# Featured_Tag_RBS020902T.net
KiCad netlist of a schematic drawn in Altium Designer
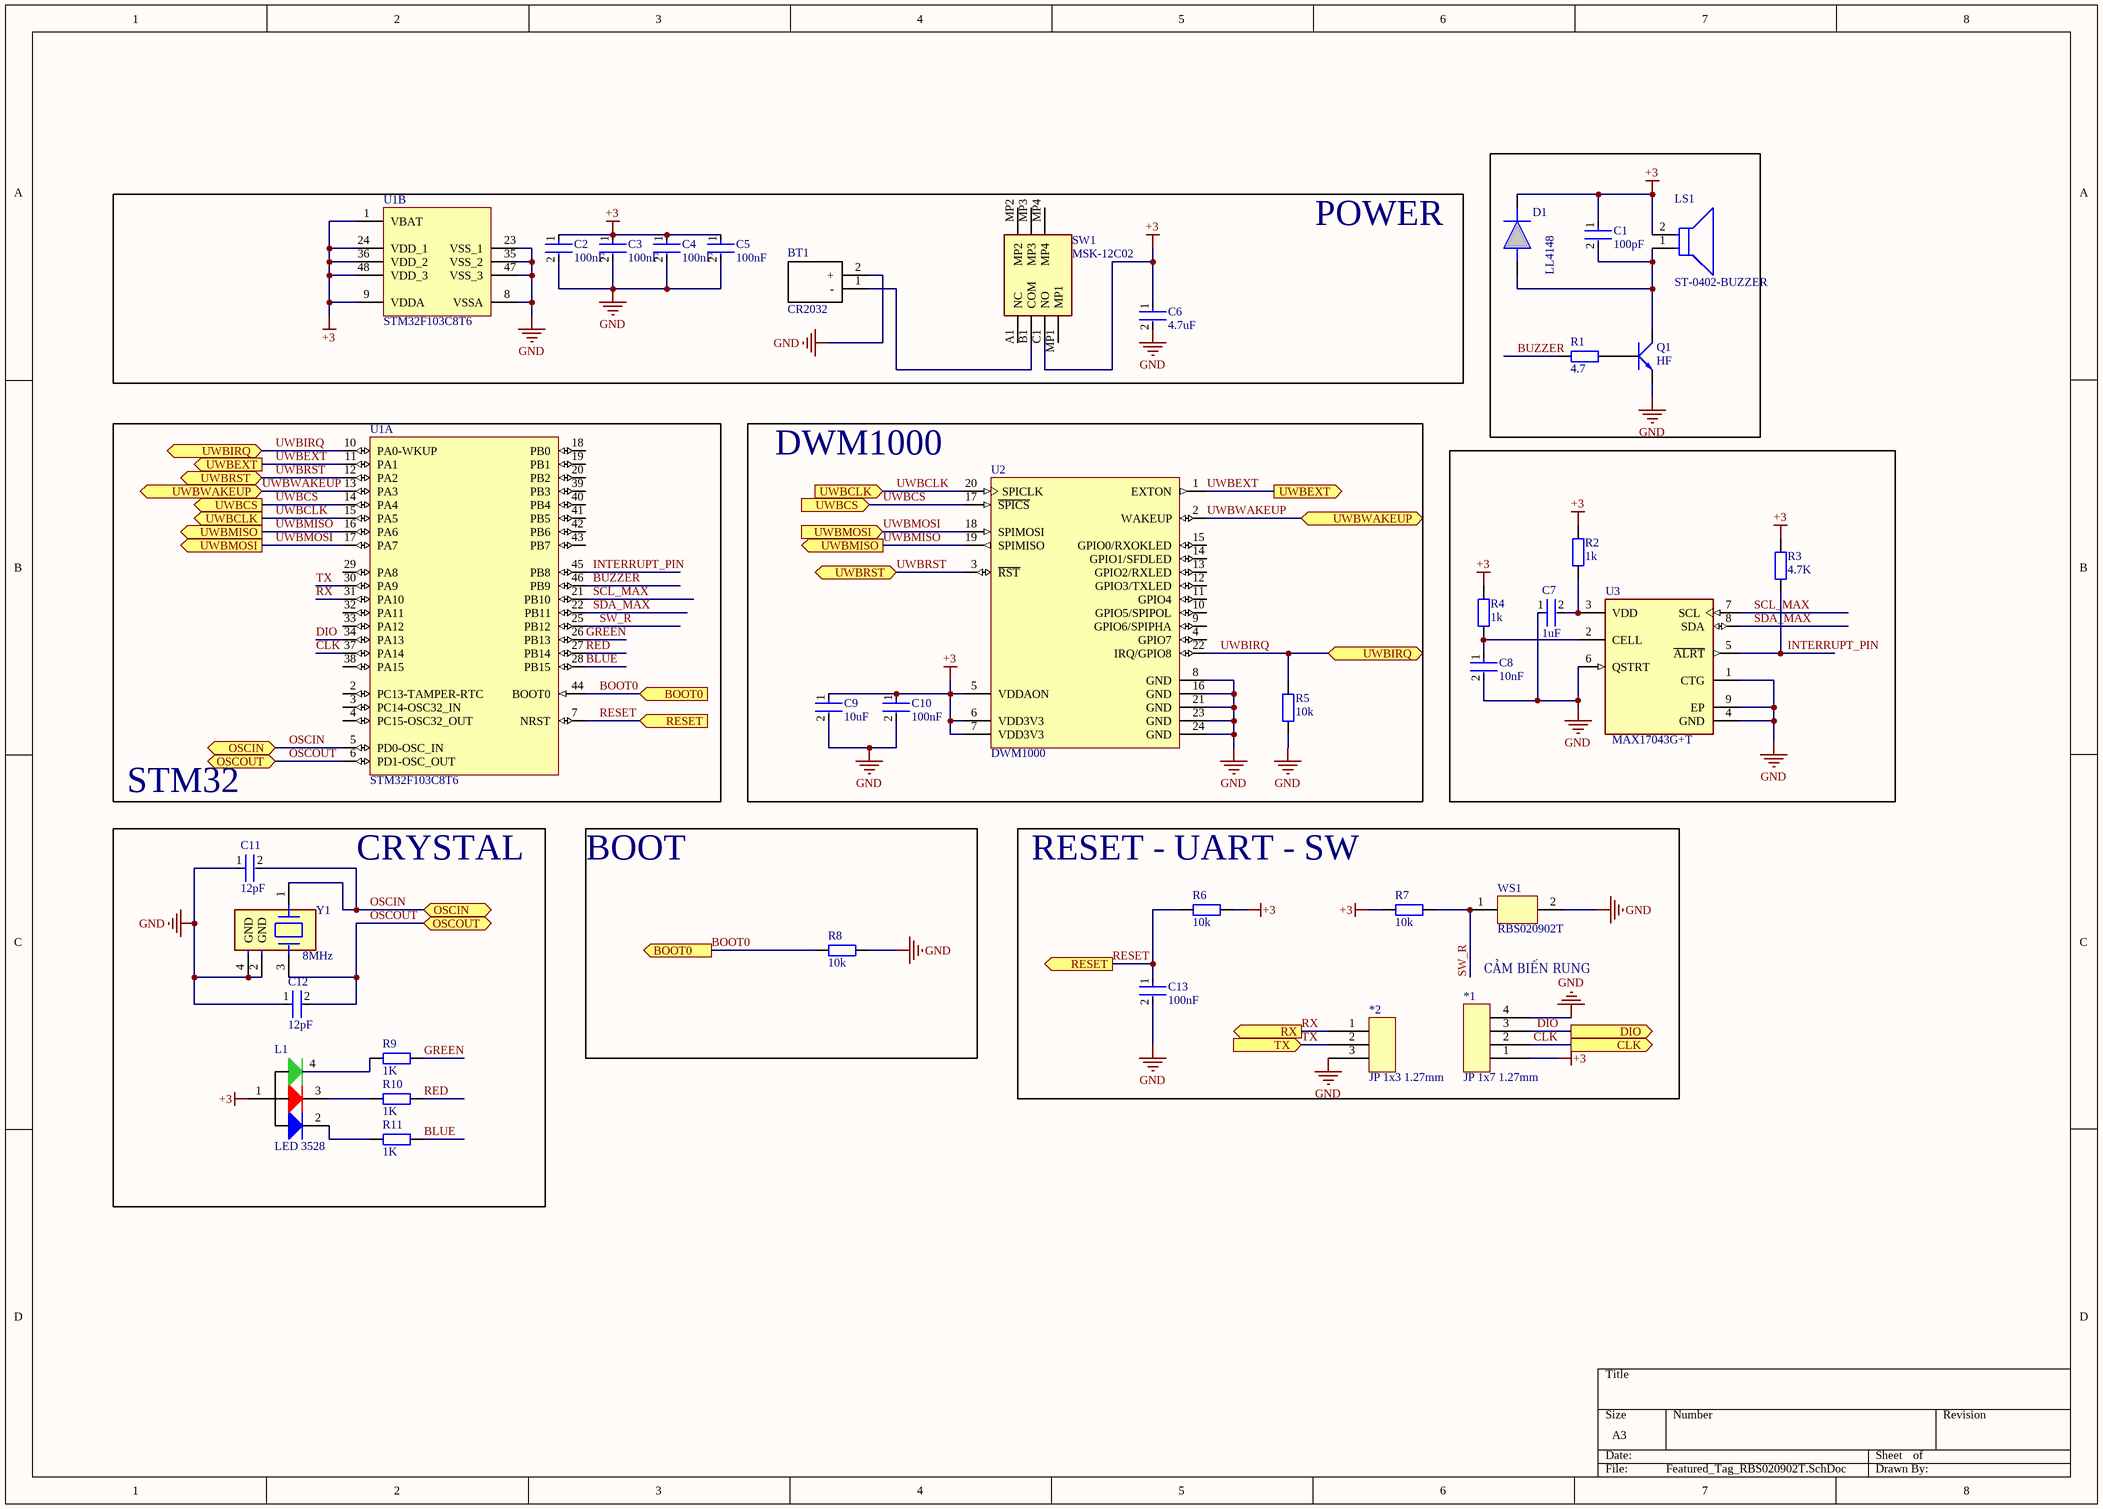
[diagram p0: Featured_Tag_RBS020902T.SchDoc]

(export (version "E")
  (design (tool "Eeschema 10.0.6"))
  (components
    (comp (ref "*1")
      (value "JP 1x7 1.27mm")
      (footprint "JP 1x4 1.27mm")
      (libsource (lib "Schlib1") (part "JP 1x7 1.27mm"))
    )
    (comp (ref "*2")
      (value "JP 1x3 1.27mm")
      (footprint "JP 1x3 1.27mm")
      (libsource (lib "Schlib1") (part "JP 1x3 1.27mm"))
    )
    (comp (ref "BT1")
      (value "CR2032")
      (footprint "SamacSys:CR2450NFHLF")
      (description "Battery")
      (fields
        (field (name "MANUFACTURER_PART_NUMBER") "CR2450NFH-LF")
        (field (name "MOUSER PART NUMBER") "614-CR2450NFH-LF")
      )
      (libsource (lib "*") (part "CR2450NFH-LF"))
    )
    (comp (ref "C1")
      (value "100pF")
      (footprint "FP-0603-L_1_6_0_15-W_0_81-MFG")
      (description "General Purpose Ceramic Capacitor, 0603, 33nF, 5%, X7R, 15%, 16V")
      (fields (field (name "TOLERANCE") "5%"))
      (libsource (lib "Altium Content Vault") (part "02cd4be3c70576c341d710602a673aa"))
    )
    (comp (ref "C2")
      (value "100nF")
      (footprint "FP-0603-L_1_6_0_15-W_0_81-MFG")
      (description "General Purpose Ceramic Capacitor, 0603, 33nF, 5%, X7R, 15%, 16V")
      (fields (field (name "TOLERANCE") "5%"))
      (libsource (lib "Altium Content Vault") (part "02cd4be3c70576c341d710602a673aa"))
    )
    (comp (ref "C3")
      (value "100nF")
      (footprint "FP-0603-L_1_6_0_15-W_0_81-MFG")
      (description "General Purpose Ceramic Capacitor, 0603, 33nF, 5%, X7R, 15%, 16V")
      (fields (field (name "TOLERANCE") "5%"))
      (libsource (lib "Altium Content Vault") (part "02cd4be3c70576c341d710602a673aa"))
    )
    (comp (ref "C4")
      (value "100nF")
      (footprint "FP-0603-L_1_6_0_15-W_0_81-MFG")
      (description "General Purpose Ceramic Capacitor, 0603, 33nF, 5%, X7R, 15%, 16V")
      (fields (field (name "TOLERANCE") "5%"))
      (libsource (lib "Altium Content Vault") (part "02cd4be3c70576c341d710602a673aa"))
    )
    (comp (ref "C5")
      (value "100nF")
      (footprint "FP-0603-L_1_6_0_15-W_0_81-MFG")
      (description "General Purpose Ceramic Capacitor, 0603, 33nF, 5%, X7R, 15%, 16V")
      (fields (field (name "TOLERANCE") "5%"))
      (libsource (lib "Altium Content Vault") (part "02cd4be3c70576c341d710602a673aa"))
    )
    (comp (ref "C6")
      (value "4.7uF")
      (footprint "FP-0603-L_1_6_0_15-W_0_81-MFG")
      (description "General Purpose Ceramic Capacitor, 0603, 33nF, 5%, X7R, 15%, 16V")
      (fields (field (name "TOLERANCE") "5%"))
      (libsource (lib "Altium Content Vault") (part "02cd4be3c70576c341d710602a673aa"))
    )
    (comp (ref "C7")
      (value "1uF")
      (footprint "FP-0603-L_1_6_0_15-W_0_81-MFG")
      (description "General Purpose Ceramic Capacitor, 0603, 33nF, 5%, X7R, 15%, 16V")
      (fields (field (name "TOLERANCE") "5%"))
      (libsource (lib "Altium Content Vault") (part "02cd4be3c70576c341d710602a673aa"))
    )
    (comp (ref "C8")
      (value "10nF")
      (footprint "FP-0603-L_1_6_0_15-W_0_81-MFG")
      (description "General Purpose Ceramic Capacitor, 0603, 33nF, 5%, X7R, 15%, 16V")
      (fields (field (name "TOLERANCE") "5%"))
      (libsource (lib "Altium Content Vault") (part "02cd4be3c70576c341d710602a673aa"))
    )
    (comp (ref "C9")
      (value "10uF")
      (footprint "FP-0603-L_1_6_0_15-W_0_81-MFG")
      (description "General Purpose Ceramic Capacitor, 0603, 33nF, 5%, X7R, 15%, 16V")
      (fields (field (name "TOLERANCE") "5%"))
      (libsource (lib "Altium Content Vault") (part "02cd4be3c70576c341d710602a673aa"))
    )
    (comp (ref "C10")
      (value "100nF")
      (footprint "FP-0603-L_1_6_0_15-W_0_81-MFG")
      (description "General Purpose Ceramic Capacitor, 0603, 33nF, 5%, X7R, 15%, 16V")
      (fields (field (name "TOLERANCE") "5%"))
      (libsource (lib "Altium Content Vault") (part "02cd4be3c70576c341d710602a673aa"))
    )
    (comp (ref "C11")
      (value "12pF")
      (footprint "FP-0603-L_1_6_0_15-W_0_81-MFG")
      (description "General Purpose Ceramic Capacitor, 0603, 33nF, 5%, X7R, 15%, 16V")
      (fields (field (name "TOLERANCE") "5%"))
      (libsource (lib "Altium Content Vault") (part "02cd4be3c70576c341d710602a673aa"))
    )
    (comp (ref "C12")
      (value "12pF")
      (footprint "FP-0603-L_1_6_0_15-W_0_81-MFG")
      (description "General Purpose Ceramic Capacitor, 0603, 33nF, 5%, X7R, 15%, 16V")
      (fields (field (name "TOLERANCE") "5%"))
      (libsource (lib "Altium Content Vault") (part "02cd4be3c70576c341d710602a673aa"))
    )
    (comp (ref "C13")
      (value "100nF")
      (footprint "FP-0603-L_1_6_0_15-W_0_81-MFG")
      (description "General Purpose Ceramic Capacitor, 0603, 33nF, 5%, X7R, 15%, 16V")
      (fields (field (name "TOLERANCE") "5%"))
      (libsource (lib "Altium Content Vault") (part "02cd4be3c70576c341d710602a673aa"))
    )
    (comp (ref "D1")
      (value "LL4148")
      (footprint "SOD-80")
      (description "Vishay LL4148-GS18 Switching Diode, 300mA, 2-Pin MiniMELF")
      (fields
        (field (name "MANUFACTURER_PART_NUMBER") "LL4148-GS18")
        (field (name "MOUSER PART NUMBER") "78-LL4148-GS18")
      )
      (libsource (lib "LL4148-GS18") (part "LL4148-GS18"))
    )
    (comp (ref "L1")
      (value "LED 3528")
      (footprint "LED RGB 3528")
      (description "Dán")
      (libsource (lib "Altium_Lib_by_KhueNguyenCreator") (part "LED 3528 RGB"))
    )
    (comp (ref "LS1")
      (value "ST-0402-BUZZER")
      (footprint "FP-ST-0402T-MFG")
      (description "AUDIO MAGNETIC XDCR 2-4V SMD")
      (fields
        (field (name "MANUFACTURER") "Soberton Inc.")
        (field (name "MANUFACTURER PART NUMBER") "ST-0402T")
      )
      (libsource (lib "Altium Content Vault") (part "e749a21513d54f03b70f810f265f423"))
    )
    (comp (ref "Q1")
      (value "HF")
      (footprint "SOT23")
      (description "NPN transistor")
      (libsource (lib "Altium_Lib_by_KhueNguyenCreator") (part "C1815 HF SMD"))
    )
    (comp (ref "R1")
      (value "4.7")
      (footprint "tro smd 0603")
      (description "Dán")
      (libsource (lib "Altium_Lib_by_KhueNguyenCreator") (part "Tro 0603 5% 1k"))
    )
    (comp (ref "R2")
      (value "1k")
      (footprint "tro smd 0603")
      (description "Dán")
      (libsource (lib "Altium_Lib_by_KhueNguyenCreator") (part "Tro 0603 5% 1k"))
    )
    (comp (ref "R3")
      (value "4.7K")
      (footprint "tro smd 0603")
      (description "Dán")
      (libsource (lib "Altium_Lib_by_KhueNguyenCreator") (part "Tro 0603 5% 1k"))
    )
    (comp (ref "R4")
      (value "1k")
      (footprint "tro smd 0603")
      (description "Dán")
      (libsource (lib "Altium_Lib_by_KhueNguyenCreator") (part "Tro 0603 5% 1k"))
    )
    (comp (ref "R5")
      (value "10k")
      (footprint "tro smd 0603")
      (description "Dán")
      (libsource (lib "Altium_Lib_by_KhueNguyenCreator") (part "Tro 0603 5% 10k"))
    )
    (comp (ref "R6")
      (value "10k")
      (footprint "tro smd 0603")
      (description "Dán")
      (libsource (lib "Altium_Lib_by_KhueNguyenCreator") (part "Tro 0603 5% 10k"))
    )
    (comp (ref "R7")
      (value "10k")
      (footprint "tro smd 0603")
      (description "Dán")
      (libsource (lib "Altium_Lib_by_KhueNguyenCreator") (part "Tro 0603 5% 10k"))
    )
    (comp (ref "R8")
      (value "10k")
      (footprint "tro smd 0603")
      (description "Dán")
      (libsource (lib "Altium_Lib_by_KhueNguyenCreator") (part "Tro 0603 5% 10k"))
    )
    (comp (ref "R9")
      (value "1K")
      (footprint "tro smd 0603")
      (description "Dán")
      (libsource (lib "Altium_Lib_by_KhueNguyenCreator") (part "Tro 0603 5% 100R"))
    )
    (comp (ref "R10")
      (value "1K")
      (footprint "tro smd 0603")
      (description "Dán")
      (libsource (lib "Altium_Lib_by_KhueNguyenCreator") (part "Tro 0603 5% 150R"))
    )
    (comp (ref "R11")
      (value "1K")
      (footprint "tro smd 0603")
      (description "Dán")
      (libsource (lib "Altium_Lib_by_KhueNguyenCreator") (part "Tro 0603 5% 100R"))
    )
    (comp (ref "SW1")
      (value "MSK-12C02")
      (footprint "sw_msk_12c02")
      (libsource (lib "Integrated_Library1") (part "MSK-12C02"))
    )
    (comp (ref "U1")
      (value "STM32F103C8T6")
      (footprint "STM-LQFP48_L")
      (libsource (lib "Altium Content Vault") (part "MC-ARM-STM32F103X8_B-SQ48"))
    )
    (comp (ref "U2")
      (value "DWM1000")
      (footprint "DECW-DWM1000-24_V")
      (description "DW M1000 IEEE 802.15.4 -2011 UWB Transceiver Module")
      (fields (field (name "MANUFACTURER") "Decawave"))
      (libsource (lib "Altium Content Vault") (part "DECW-DWM1000-24"))
    )
    (comp (ref "U3")
      (value "MAX17043G+T")
      (footprint "FP-T823-1-MFG")
      (description "IC 2-WIRE FG MODEL GAUGE LO BATT")
      (fields
        (field (name "MANUFACTURER") "Maxim")
        (field (name "OCTOPART") "https://octopart.com/max17043g%2Bt-maxim+integrated-43979038")
      )
      (libsource (lib "Altium Content Vault") (part "35642440c5a18a865b7fad9439d5373"))
    )
    (comp (ref "WS1")
      (value "RBS020902T")
      (footprint "RBS020902T")
      (libsource (lib "Schlib1") (part "RBS020902T"))
    )
    (comp (ref "Y1")
      (value "8MHz")
      (footprint "FP-7M-MFG")
      (description "Crystal 26MHz, 30ppm, 18pF, 50Ω")
      (fields (field (name "TOLERANCE") "30ppm"))
      (libsource (lib "Altium Content Vault") (part "41079aabb0e87794b56622915be14ed"))
    )
  )
  (nets
    (net (code "1") (name "+3") (class "Default")
      (node (ref "*1") (pin "1") (pintype "passive"))
      (node (ref "C1") (pin "1") (pinfunction "1_1") (pintype "passive"))
      (node (ref "C10") (pin "1") (pinfunction "1_1") (pintype "passive"))
      (node (ref "C2") (pin "1") (pinfunction "1_1") (pintype "passive"))
      (node (ref "C3") (pin "1") (pinfunction "1_1") (pintype "passive"))
      (node (ref "C4") (pin "1") (pinfunction "1_1") (pintype "passive"))
      (node (ref "C5") (pin "1") (pinfunction "1_1") (pintype "passive"))
      (node (ref "C6") (pin "1") (pinfunction "1_1") (pintype "passive"))
      (node (ref "C9") (pin "1") (pinfunction "1_1") (pintype "passive"))
      (node (ref "D1") (pin "1") (pinfunction "K_1") (pintype "passive"))
      (node (ref "L1") (pin "1") (pintype "passive"))
      (node (ref "LS1") (pin "2") (pinfunction "A_2") (pintype "passive"))
      (node (ref "R2") (pin "2") (pinfunction "2_2") (pintype "passive"))
      (node (ref "R3") (pin "2") (pinfunction "2_2") (pintype "passive"))
      (node (ref "R4") (pin "2") (pinfunction "2_2") (pintype "passive"))
      (node (ref "R6") (pin "1") (pinfunction "1_1") (pintype "passive"))
      (node (ref "R7") (pin "2") (pinfunction "2_2") (pintype "passive"))
      (node (ref "SW1") (pin "C1") (pinfunction "NO_C1") (pintype "passive"))
      (node (ref "U1") (pin "1") (pinfunction "VBAT_1") (pintype "power_in"))
      (node (ref "U1") (pin "24") (pinfunction "VDD_1_24") (pintype "power_in"))
      (node (ref "U1") (pin "36") (pinfunction "VDD_2_36") (pintype "power_in"))
      (node (ref "U1") (pin "48") (pinfunction "VDD_3_48") (pintype "power_in"))
      (node (ref "U1") (pin "9") (pinfunction "VDDA_9") (pintype "power_in"))
      (node (ref "U2") (pin "5") (pinfunction "VDDAON_5") (pintype "power_in"))
      (node (ref "U2") (pin "6") (pinfunction "VDD3V3_6") (pintype "power_in"))
      (node (ref "U2") (pin "7") (pinfunction "VDD3V3_7") (pintype "power_in"))
    )
    (net (code "2") (name "/BLUE") (class "Default")
      (node (ref "R11") (pin "2") (pinfunction "2_2") (pintype "passive"))
      (node (ref "U1") (pin "28") (pinfunction "PB15_28") (pintype "bidirectional"))
    )
    (net (code "3") (name "/BOOT0") (class "Default")
      (node (ref "R8") (pin "2") (pinfunction "2_2") (pintype "passive"))
      (node (ref "U1") (pin "44") (pinfunction "BOOT0_44") (pintype "input"))
    )
    (net (code "4") (name "/BUZZER") (class "Default")
      (node (ref "R1") (pin "2") (pinfunction "2_2") (pintype "passive"))
      (node (ref "U1") (pin "46") (pinfunction "PB9_46") (pintype "bidirectional"))
    )
    (net (code "5") (name "/CLK") (class "Default")
      (node (ref "*1") (pin "2") (pintype "passive"))
      (node (ref "U1") (pin "37") (pinfunction "PA14_37") (pintype "bidirectional"))
    )
    (net (code "6") (name "/DIO") (class "Default")
      (node (ref "*1") (pin "3") (pintype "passive"))
      (node (ref "U1") (pin "34") (pinfunction "PA13_34") (pintype "bidirectional"))
    )
    (net (code "7") (name "/GREEN") (class "Default")
      (node (ref "R9") (pin "2") (pinfunction "2_2") (pintype "passive"))
      (node (ref "U1") (pin "26") (pinfunction "PB13_26") (pintype "bidirectional"))
    )
    (net (code "8") (name "/INTERRUPT_PIN") (class "Default")
      (node (ref "R3") (pin "1") (pinfunction "1_1") (pintype "passive"))
      (node (ref "U1") (pin "45") (pinfunction "PB8_45") (pintype "bidirectional"))
      (node (ref "U3") (pin "5") (pinfunction "~{ALRT}_5") (pintype "output"))
    )
    (net (code "9") (name "/OSCIN") (class "Default")
      (node (ref "C11") (pin "2") (pinfunction "2_2") (pintype "passive"))
      (node (ref "U1") (pin "5") (pinfunction "PD0-OSC_IN_5") (pintype "bidirectional"))
      (node (ref "Y1") (pin "1") (pinfunction "1_1") (pintype "passive"))
    )
    (net (code "10") (name "/OSCOUT") (class "Default")
      (node (ref "C12") (pin "2") (pinfunction "2_2") (pintype "passive"))
      (node (ref "U1") (pin "6") (pinfunction "PD1-OSC_OUT_6") (pintype "bidirectional"))
      (node (ref "Y1") (pin "3") (pinfunction "3_3") (pintype "passive"))
    )
    (net (code "11") (name "/RED") (class "Default")
      (node (ref "R10") (pin "2") (pinfunction "2_2") (pintype "passive"))
      (node (ref "U1") (pin "27") (pinfunction "PB14_27") (pintype "bidirectional"))
    )
    (net (code "12") (name "/RESET") (class "Default")
      (node (ref "C13") (pin "1") (pinfunction "1_1") (pintype "passive"))
      (node (ref "R6") (pin "2") (pinfunction "2_2") (pintype "passive"))
      (node (ref "U1") (pin "7") (pinfunction "NRST_7") (pintype "bidirectional"))
    )
    (net (code "13") (name "/RX") (class "Default")
      (node (ref "*2") (pin "1") (pintype "passive"))
      (node (ref "U1") (pin "31") (pinfunction "PA10_31") (pintype "bidirectional"))
    )
    (net (code "14") (name "/SCL_MAX") (class "Default")
      (node (ref "U1") (pin "21") (pinfunction "PB10_21") (pintype "bidirectional"))
      (node (ref "U3") (pin "7") (pinfunction "SCL_7") (pintype "input"))
    )
    (net (code "15") (name "/SDA_MAX") (class "Default")
      (node (ref "U1") (pin "22") (pinfunction "PB11_22") (pintype "bidirectional"))
      (node (ref "U3") (pin "8") (pinfunction "SDA_8") (pintype "bidirectional"))
    )
    (net (code "16") (name "/SW_R") (class "Default")
      (node (ref "R7") (pin "1") (pinfunction "1_1") (pintype "passive"))
      (node (ref "U1") (pin "25") (pinfunction "PB12_25") (pintype "bidirectional"))
      (node (ref "WS1") (pin "1") (pinfunction "1_1") (pintype "passive"))
    )
    (net (code "17") (name "/TX") (class "Default")
      (node (ref "*2") (pin "2") (pintype "passive"))
      (node (ref "U1") (pin "30") (pinfunction "PA9_30") (pintype "bidirectional"))
    )
    (net (code "18") (name "/UWBCLK") (class "Default")
      (node (ref "U1") (pin "15") (pinfunction "PA5_15") (pintype "bidirectional"))
      (node (ref "U2") (pin "20") (pinfunction "SPICLK_20") (pintype "input"))
    )
    (net (code "19") (name "/UWBCS") (class "Default")
      (node (ref "U1") (pin "14") (pinfunction "PA4_14") (pintype "bidirectional"))
      (node (ref "U2") (pin "17") (pinfunction "~{SPICS}_17") (pintype "input"))
    )
    (net (code "20") (name "/UWBEXT") (class "Default")
      (node (ref "U1") (pin "11") (pinfunction "PA1_11") (pintype "bidirectional"))
      (node (ref "U2") (pin "1") (pinfunction "EXTON_1") (pintype "output"))
    )
    (net (code "21") (name "/UWBIRQ") (class "Default")
      (node (ref "R5") (pin "2") (pinfunction "2_2") (pintype "passive"))
      (node (ref "U1") (pin "10") (pinfunction "PA0-WKUP_10") (pintype "bidirectional"))
      (node (ref "U2") (pin "22") (pinfunction "IRQ/GPIO8_22") (pintype "bidirectional"))
    )
    (net (code "22") (name "/UWBMISO") (class "Default")
      (node (ref "U1") (pin "16") (pinfunction "PA6_16") (pintype "bidirectional"))
      (node (ref "U2") (pin "19") (pinfunction "SPIMISO_19") (pintype "output"))
    )
    (net (code "23") (name "/UWBMOSI") (class "Default")
      (node (ref "U1") (pin "17") (pinfunction "PA7_17") (pintype "bidirectional"))
      (node (ref "U2") (pin "18") (pinfunction "SPIMOSI_18") (pintype "input"))
    )
    (net (code "24") (name "/UWBRST") (class "Default")
      (node (ref "U1") (pin "12") (pinfunction "PA2_12") (pintype "bidirectional"))
      (node (ref "U2") (pin "3") (pinfunction "~{RST}_3") (pintype "bidirectional"))
    )
    (net (code "25") (name "/UWBWAKEUP") (class "Default")
      (node (ref "U1") (pin "13") (pinfunction "PA3_13") (pintype "bidirectional"))
      (node (ref "U2") (pin "2") (pinfunction "WAKEUP_2") (pintype "bidirectional"))
    )
    (net (code "26") (name "GND") (class "Default")
      (node (ref "*1") (pin "4") (pintype "passive"))
      (node (ref "*2") (pin "3") (pintype "passive"))
      (node (ref "BT1") (pin "2") (pinfunction "+_2") (pintype "passive"))
      (node (ref "C10") (pin "2") (pinfunction "2_2") (pintype "passive"))
      (node (ref "C11") (pin "1") (pinfunction "1_1") (pintype "passive"))
      (node (ref "C12") (pin "1") (pinfunction "1_1") (pintype "passive"))
      (node (ref "C13") (pin "2") (pinfunction "2_2") (pintype "passive"))
      (node (ref "C2") (pin "2") (pinfunction "2_2") (pintype "passive"))
      (node (ref "C3") (pin "2") (pinfunction "2_2") (pintype "passive"))
      (node (ref "C4") (pin "2") (pinfunction "2_2") (pintype "passive"))
      (node (ref "C5") (pin "2") (pinfunction "2_2") (pintype "passive"))
      (node (ref "C6") (pin "2") (pinfunction "2_2") (pintype "passive"))
      (node (ref "C7") (pin "1") (pinfunction "1_1") (pintype "passive"))
      (node (ref "C8") (pin "2") (pinfunction "2_2") (pintype "passive"))
      (node (ref "C9") (pin "2") (pinfunction "2_2") (pintype "passive"))
      (node (ref "Q1") (pin "2") (pinfunction "E_2") (pintype "passive"))
      (node (ref "R5") (pin "1") (pinfunction "1_1") (pintype "passive"))
      (node (ref "R8") (pin "1") (pinfunction "1_1") (pintype "passive"))
      (node (ref "U1") (pin "23") (pinfunction "VSS_1_23") (pintype "power_in"))
      (node (ref "U1") (pin "35") (pinfunction "VSS_2_35") (pintype "power_in"))
      (node (ref "U1") (pin "47") (pinfunction "VSS_3_47") (pintype "power_in"))
      (node (ref "U1") (pin "8") (pinfunction "VSSA_8") (pintype "power_in"))
      (node (ref "U2") (pin "16") (pinfunction "GND_16") (pintype "power_in"))
      (node (ref "U2") (pin "21") (pinfunction "GND_21") (pintype "power_in"))
      (node (ref "U2") (pin "23") (pinfunction "GND_23") (pintype "power_in"))
      (node (ref "U2") (pin "24") (pinfunction "GND_24") (pintype "power_in"))
      (node (ref "U2") (pin "8") (pinfunction "GND_8") (pintype "power_in"))
      (node (ref "U3") (pin "1") (pinfunction "CTG_1") (pintype "power_in"))
      (node (ref "U3") (pin "4") (pinfunction "GND_4") (pintype "power_in"))
      (node (ref "U3") (pin "6") (pinfunction "QSTRT_6") (pintype "input"))
      (node (ref "U3") (pin "9") (pinfunction "EP_9") (pintype "power_in"))
      (node (ref "WS1") (pin "2") (pinfunction "2_2") (pintype "passive"))
      (node (ref "Y1") (pin "2") (pinfunction "GND_2") (pintype "power_in"))
      (node (ref "Y1") (pin "4") (pinfunction "GND_4") (pintype "power_in"))
    )
    (net (code "27") (name "Net-(BT1--)") (class "Default")
      (node (ref "BT1") (pin "1") (pinfunction "-_1") (pintype "passive"))
      (node (ref "SW1") (pin "B1") (pinfunction "COM_B1") (pintype "passive"))
    )
    (net (code "28") (name "Net-(D1-A)") (class "Default")
      (node (ref "C1") (pin "2") (pinfunction "2_2") (pintype "passive"))
      (node (ref "D1") (pin "2") (pinfunction "A_2") (pintype "passive"))
      (node (ref "LS1") (pin "1") (pinfunction "C_1") (pintype "passive"))
      (node (ref "Q1") (pin "3") (pinfunction "C_3") (pintype "passive"))
    )
    (net (code "29") (name "Net-(L1-Pad2)") (class "Default")
      (node (ref "L1") (pin "2") (pintype "passive"))
      (node (ref "R11") (pin "1") (pinfunction "1_1") (pintype "passive"))
    )
    (net (code "30") (name "Net-(L1-Pad3)") (class "Default")
      (node (ref "L1") (pin "3") (pintype "passive"))
      (node (ref "R10") (pin "1") (pinfunction "1_1") (pintype "passive"))
    )
    (net (code "31") (name "Net-(L1-Pad4)") (class "Default")
      (node (ref "L1") (pin "4") (pintype "passive"))
      (node (ref "R9") (pin "1") (pinfunction "1_1") (pintype "passive"))
    )
    (net (code "32") (name "Net-(Q1-B)") (class "Default")
      (node (ref "Q1") (pin "1") (pinfunction "B_1") (pintype "passive"))
      (node (ref "R1") (pin "1") (pinfunction "1_1") (pintype "passive"))
    )
    (net (code "33") (name "Net-(U3-CELL)") (class "Default")
      (node (ref "C8") (pin "1") (pinfunction "1_1") (pintype "passive"))
      (node (ref "R4") (pin "1") (pinfunction "1_1") (pintype "passive"))
      (node (ref "U3") (pin "2") (pinfunction "CELL_2") (pintype "passive"))
    )
    (net (code "34") (name "Net-(U3-VDD)") (class "Default")
      (node (ref "C7") (pin "2") (pinfunction "2_2") (pintype "passive"))
      (node (ref "R2") (pin "1") (pinfunction "1_1") (pintype "passive"))
      (node (ref "U3") (pin "3") (pinfunction "VDD_3") (pintype "power_in"))
    )
    (net (code "35") (name "unconnected-(SW1-NC-PadA1)") (class "Default")
      (node (ref "SW1") (pin "A1") (pinfunction "NC_A1") (pintype "passive"))
    )
    (net (code "36") (name "unconnected-(SW1-PadMP1)") (class "Default")
      (node (ref "SW1") (pin "MP1") (pinfunction "MP1_MP1") (pintype "passive"))
    )
    (net (code "37") (name "unconnected-(SW1-PadMP2)") (class "Default")
      (node (ref "SW1") (pin "MP2") (pinfunction "MP2_MP2") (pintype "passive"))
    )
    (net (code "38") (name "unconnected-(SW1-PadMP3)") (class "Default")
      (node (ref "SW1") (pin "MP3") (pinfunction "MP3_MP3") (pintype "passive"))
    )
    (net (code "39") (name "unconnected-(SW1-PadMP4)") (class "Default")
      (node (ref "SW1") (pin "MP4") (pinfunction "MP4_MP4") (pintype "passive"))
    )
    (net (code "40") (name "unconnected-(U1A-PA8-Pad29)") (class "Default")
      (node (ref "U1") (pin "29") (pinfunction "PA8_29") (pintype "bidirectional"))
    )
    (net (code "41") (name "unconnected-(U1A-PA11-Pad32)") (class "Default")
      (node (ref "U1") (pin "32") (pinfunction "PA11_32") (pintype "bidirectional"))
    )
    (net (code "42") (name "unconnected-(U1A-PA12-Pad33)") (class "Default")
      (node (ref "U1") (pin "33") (pinfunction "PA12_33") (pintype "bidirectional"))
    )
    (net (code "43") (name "unconnected-(U1A-PA15-Pad38)") (class "Default")
      (node (ref "U1") (pin "38") (pinfunction "PA15_38") (pintype "bidirectional"))
    )
    (net (code "44") (name "unconnected-(U1A-PB0-Pad18)") (class "Default")
      (node (ref "U1") (pin "18") (pinfunction "PB0_18") (pintype "bidirectional"))
    )
    (net (code "45") (name "unconnected-(U1A-PB1-Pad19)") (class "Default")
      (node (ref "U1") (pin "19") (pinfunction "PB1_19") (pintype "bidirectional"))
    )
    (net (code "46") (name "unconnected-(U1A-PB2-Pad20)") (class "Default")
      (node (ref "U1") (pin "20") (pinfunction "PB2_20") (pintype "bidirectional"))
    )
    (net (code "47") (name "unconnected-(U1A-PB3-Pad39)") (class "Default")
      (node (ref "U1") (pin "39") (pinfunction "PB3_39") (pintype "bidirectional"))
    )
    (net (code "48") (name "unconnected-(U1A-PB4-Pad40)") (class "Default")
      (node (ref "U1") (pin "40") (pinfunction "PB4_40") (pintype "bidirectional"))
    )
    (net (code "49") (name "unconnected-(U1A-PB5-Pad41)") (class "Default")
      (node (ref "U1") (pin "41") (pinfunction "PB5_41") (pintype "bidirectional"))
    )
    (net (code "50") (name "unconnected-(U1A-PB6-Pad42)") (class "Default")
      (node (ref "U1") (pin "42") (pinfunction "PB6_42") (pintype "bidirectional"))
    )
    (net (code "51") (name "unconnected-(U1A-PB7-Pad43)") (class "Default")
      (node (ref "U1") (pin "43") (pinfunction "PB7_43") (pintype "bidirectional"))
    )
    (net (code "52") (name "unconnected-(U1A-PC13-TAMPER-RTC-Pad2)") (class "Default")
      (node (ref "U1") (pin "2") (pinfunction "PC13-TAMPER-RTC_2") (pintype "bidirectional"))
    )
    (net (code "53") (name "unconnected-(U1A-PC14-OSC32_IN-Pad3)") (class "Default")
      (node (ref "U1") (pin "3") (pinfunction "PC14-OSC32_IN_3") (pintype "bidirectional"))
    )
    (net (code "54") (name "unconnected-(U1A-PC15-OSC32_OUT-Pad4)") (class "Default")
      (node (ref "U1") (pin "4") (pinfunction "PC15-OSC32_OUT_4") (pintype "bidirectional"))
    )
    (net (code "55") (name "unconnected-(U2-GPIO0{slash}RXOKLED-Pad15)") (class "Default")
      (node (ref "U2") (pin "15") (pinfunction "GPIO0/RXOKLED_15") (pintype "bidirectional"))
    )
    (net (code "56") (name "unconnected-(U2-GPIO1{slash}SFDLED-Pad14)") (class "Default")
      (node (ref "U2") (pin "14") (pinfunction "GPIO1/SFDLED_14") (pintype "bidirectional"))
    )
    (net (code "57") (name "unconnected-(U2-GPIO2{slash}RXLED-Pad13)") (class "Default")
      (node (ref "U2") (pin "13") (pinfunction "GPIO2/RXLED_13") (pintype "bidirectional"))
    )
    (net (code "58") (name "unconnected-(U2-GPIO3{slash}TXLED-Pad12)") (class "Default")
      (node (ref "U2") (pin "12") (pinfunction "GPIO3/TXLED_12") (pintype "bidirectional"))
    )
    (net (code "59") (name "unconnected-(U2-GPIO4-Pad11)") (class "Default")
      (node (ref "U2") (pin "11") (pinfunction "GPIO4_11") (pintype "bidirectional"))
    )
    (net (code "60") (name "unconnected-(U2-GPIO5{slash}SPIPOL-Pad10)") (class "Default")
      (node (ref "U2") (pin "10") (pinfunction "GPIO5/SPIPOL_10") (pintype "bidirectional"))
    )
    (net (code "61") (name "unconnected-(U2-GPIO6{slash}SPIPHA-Pad9)") (class "Default")
      (node (ref "U2") (pin "9") (pinfunction "GPIO6/SPIPHA_9") (pintype "bidirectional"))
    )
    (net (code "62") (name "unconnected-(U2-GPIO7-Pad4)") (class "Default")
      (node (ref "U2") (pin "4") (pinfunction "GPIO7_4") (pintype "bidirectional"))
    )
  )
)
